# reefpi_pico_fet.net
KiCad netlist of a schematic drawn in Altium Designer
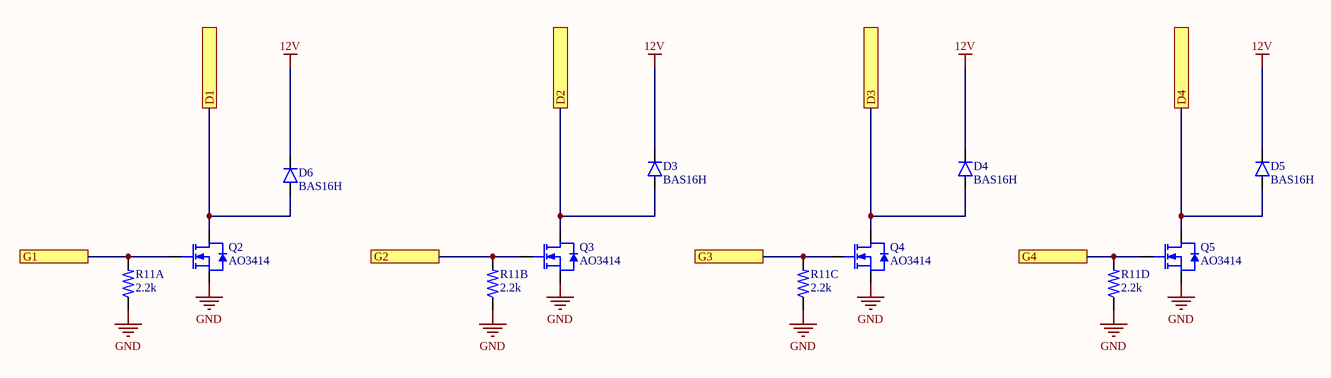
[diagram p0: reefpi_pico_fet.SchDoc]

(export (version "E")
  (design (tool "Eeschema 10.0.6"))
  (components
    (comp (ref "D3")
      (value "BAS16H")
      (footprint "SOD323R_INFINEON")
      (libsource (lib "general") (part "DIODE"))
    )
    (comp (ref "D4")
      (value "BAS16H")
      (footprint "SOD323R_INFINEON")
      (libsource (lib "general") (part "DIODE"))
    )
    (comp (ref "D5")
      (value "BAS16H")
      (footprint "SOD323R_INFINEON")
      (libsource (lib "general") (part "DIODE"))
    )
    (comp (ref "D6")
      (value "BAS16H")
      (footprint "SOD323R_INFINEON")
      (libsource (lib "general") (part "DIODE"))
    )
    (comp (ref "Q2") (value "AO3414") (footprint "SOT23-3") (libsource (lib "general") (part "NFET")))
    (comp (ref "Q3") (value "AO3414") (footprint "SOT23-3") (libsource (lib "general") (part "NFET")))
    (comp (ref "Q4") (value "AO3414") (footprint "SOT23-3") (libsource (lib "general") (part "NFET")))
    (comp (ref "Q5") (value "AO3414") (footprint "SOT23-3") (libsource (lib "general") (part "NFET")))
    (comp (ref "R11") (value "2.2k") (footprint "R0603x4") (libsource (lib "rcl") (part "R-US-4ch")))
  )
  (nets
    (net (code "1") (name "/D1") (class "Default")
      (node (ref "D6") (pin "A") (pinfunction "A_A") (pintype "power_in"))
      (node (ref "Q2") (pin "3") (pinfunction "D_3") (pintype "passive"))
    )
    (net (code "2") (name "/D2") (class "Default")
      (node (ref "D3") (pin "A") (pinfunction "A_A") (pintype "power_in"))
      (node (ref "Q3") (pin "3") (pinfunction "D_3") (pintype "passive"))
    )
    (net (code "3") (name "/D3") (class "Default")
      (node (ref "D4") (pin "A") (pinfunction "A_A") (pintype "power_in"))
      (node (ref "Q4") (pin "3") (pinfunction "D_3") (pintype "passive"))
    )
    (net (code "4") (name "/D4") (class "Default")
      (node (ref "D5") (pin "A") (pinfunction "A_A") (pintype "power_in"))
      (node (ref "Q5") (pin "3") (pinfunction "D_3") (pintype "passive"))
    )
    (net (code "5") (name "/G1") (class "Default")
      (node (ref "Q2") (pin "1") (pinfunction "G_1") (pintype "passive"))
      (node (ref "R11") (pin "2") (pinfunction "2_2") (pintype "passive"))
    )
    (net (code "6") (name "/G2") (class "Default")
      (node (ref "Q3") (pin "1") (pinfunction "G_1") (pintype "passive"))
      (node (ref "R11") (pin "4") (pinfunction "4_4") (pintype "passive"))
    )
    (net (code "7") (name "/G3") (class "Default")
      (node (ref "Q4") (pin "1") (pinfunction "G_1") (pintype "passive"))
      (node (ref "R11") (pin "6") (pinfunction "6_6") (pintype "passive"))
    )
    (net (code "8") (name "/G4") (class "Default")
      (node (ref "Q5") (pin "1") (pinfunction "G_1") (pintype "passive"))
      (node (ref "R11") (pin "8") (pinfunction "8_8") (pintype "passive"))
    )
    (net (code "9") (name "12V") (class "Default")
      (node (ref "D3") (pin "K") (pinfunction "K_K") (pintype "power_in"))
      (node (ref "D4") (pin "K") (pinfunction "K_K") (pintype "power_in"))
      (node (ref "D5") (pin "K") (pinfunction "K_K") (pintype "power_in"))
      (node (ref "D6") (pin "K") (pinfunction "K_K") (pintype "power_in"))
    )
    (net (code "10") (name "GND") (class "Default")
      (node (ref "Q2") (pin "2") (pinfunction "S_2") (pintype "passive"))
      (node (ref "Q3") (pin "2") (pinfunction "S_2") (pintype "passive"))
      (node (ref "Q4") (pin "2") (pinfunction "S_2") (pintype "passive"))
      (node (ref "Q5") (pin "2") (pinfunction "S_2") (pintype "passive"))
      (node (ref "R11") (pin "1") (pinfunction "1_1") (pintype "passive"))
      (node (ref "R11") (pin "3") (pinfunction "3_3") (pintype "passive"))
      (node (ref "R11") (pin "5") (pinfunction "5_5") (pintype "passive"))
      (node (ref "R11") (pin "7") (pinfunction "7_7") (pintype "passive"))
    )
  )
)
